# Codeshelf-0006_v02.net
KiCad netlist of a schematic drawn in EAGLE
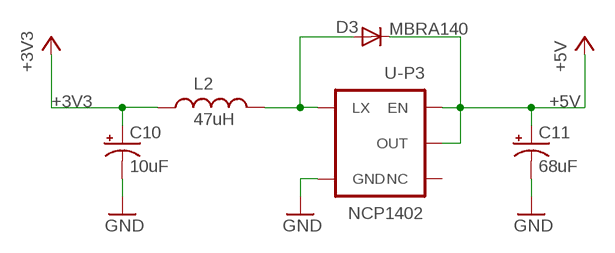
[diagram p0: schematic, sheet 1]

(export (version "E")
  (design (tool "Eeschema 10.0.6"))
  (components
    (comp (ref "C10")
      (value "10uF")
      (footprint "eagle-import:EIA3216")
      (libsource (lib "eagle-import") (part "CAP_POL1206"))
    )
    (comp (ref "C11")
      (value "68uF")
      (footprint "eagle-import:EIA3528")
      (libsource (lib "eagle-import") (part "CAP_POL3528"))
    )
    (comp (ref "D3")
      (value "MBRA140")
      (footprint "eagle-import:SMA-DIODE")
      (libsource (lib "eagle-import") (part "DIODESMA"))
    )
    (comp (ref "L2")
      (value "47uH")
      (footprint "eagle-import:CR54")
      (libsource (lib "eagle-import") (part "INDUCTORCR54"))
    )
    (comp (ref "U-P3")
      (value "NCP1402")
      (footprint "eagle-import:SOT23-5")
      (libsource (lib "eagle-import") (part "V_REG_NCP1400SOT23-5"))
    )
  )
  (nets
    (net (code "1") (name "+3V3") (class "Default")
      (node (ref "C10") (pin "A") (pinfunction "+_A") (pintype "passive"))
      (node (ref "L2") (pin "P$1") (pinfunction "1_P$1") (pintype "passive"))
    )
    (net (code "2") (name "+5V") (class "Default")
      (node (ref "C11") (pin "A") (pinfunction "+_A") (pintype "passive"))
      (node (ref "D3") (pin "C") (pinfunction "C_C") (pintype "passive"))
      (node (ref "U-P3") (pin "1") (pinfunction "EN_1") (pintype "input"))
      (node (ref "U-P3") (pin "2") (pinfunction "OUT_2") (pintype "passive"))
    )
    (net (code "3") (name "GND") (class "Default")
      (node (ref "C10") (pin "C") (pinfunction "-_C") (pintype "passive"))
      (node (ref "C11") (pin "C") (pinfunction "-_C") (pintype "passive"))
      (node (ref "U-P3") (pin "4") (pinfunction "GND_4") (pintype "input"))
    )
    (net (code "4") (name "Net-(L2-2)") (class "Default")
      (node (ref "D3") (pin "A") (pinfunction "A_A") (pintype "passive"))
      (node (ref "L2") (pin "P$2") (pinfunction "2_P$2") (pintype "passive"))
      (node (ref "U-P3") (pin "5") (pinfunction "LX_5") (pintype "input"))
    )
    (net (code "5") (name "unconnected-(U-P3-NC-Pad3)") (class "Default")
      (node (ref "U-P3") (pin "3") (pinfunction "NC_3") (pintype "input"))
    )
  )
)
